# SPI_translators.net
KiCad netlist of a schematic drawn in Altium Designer
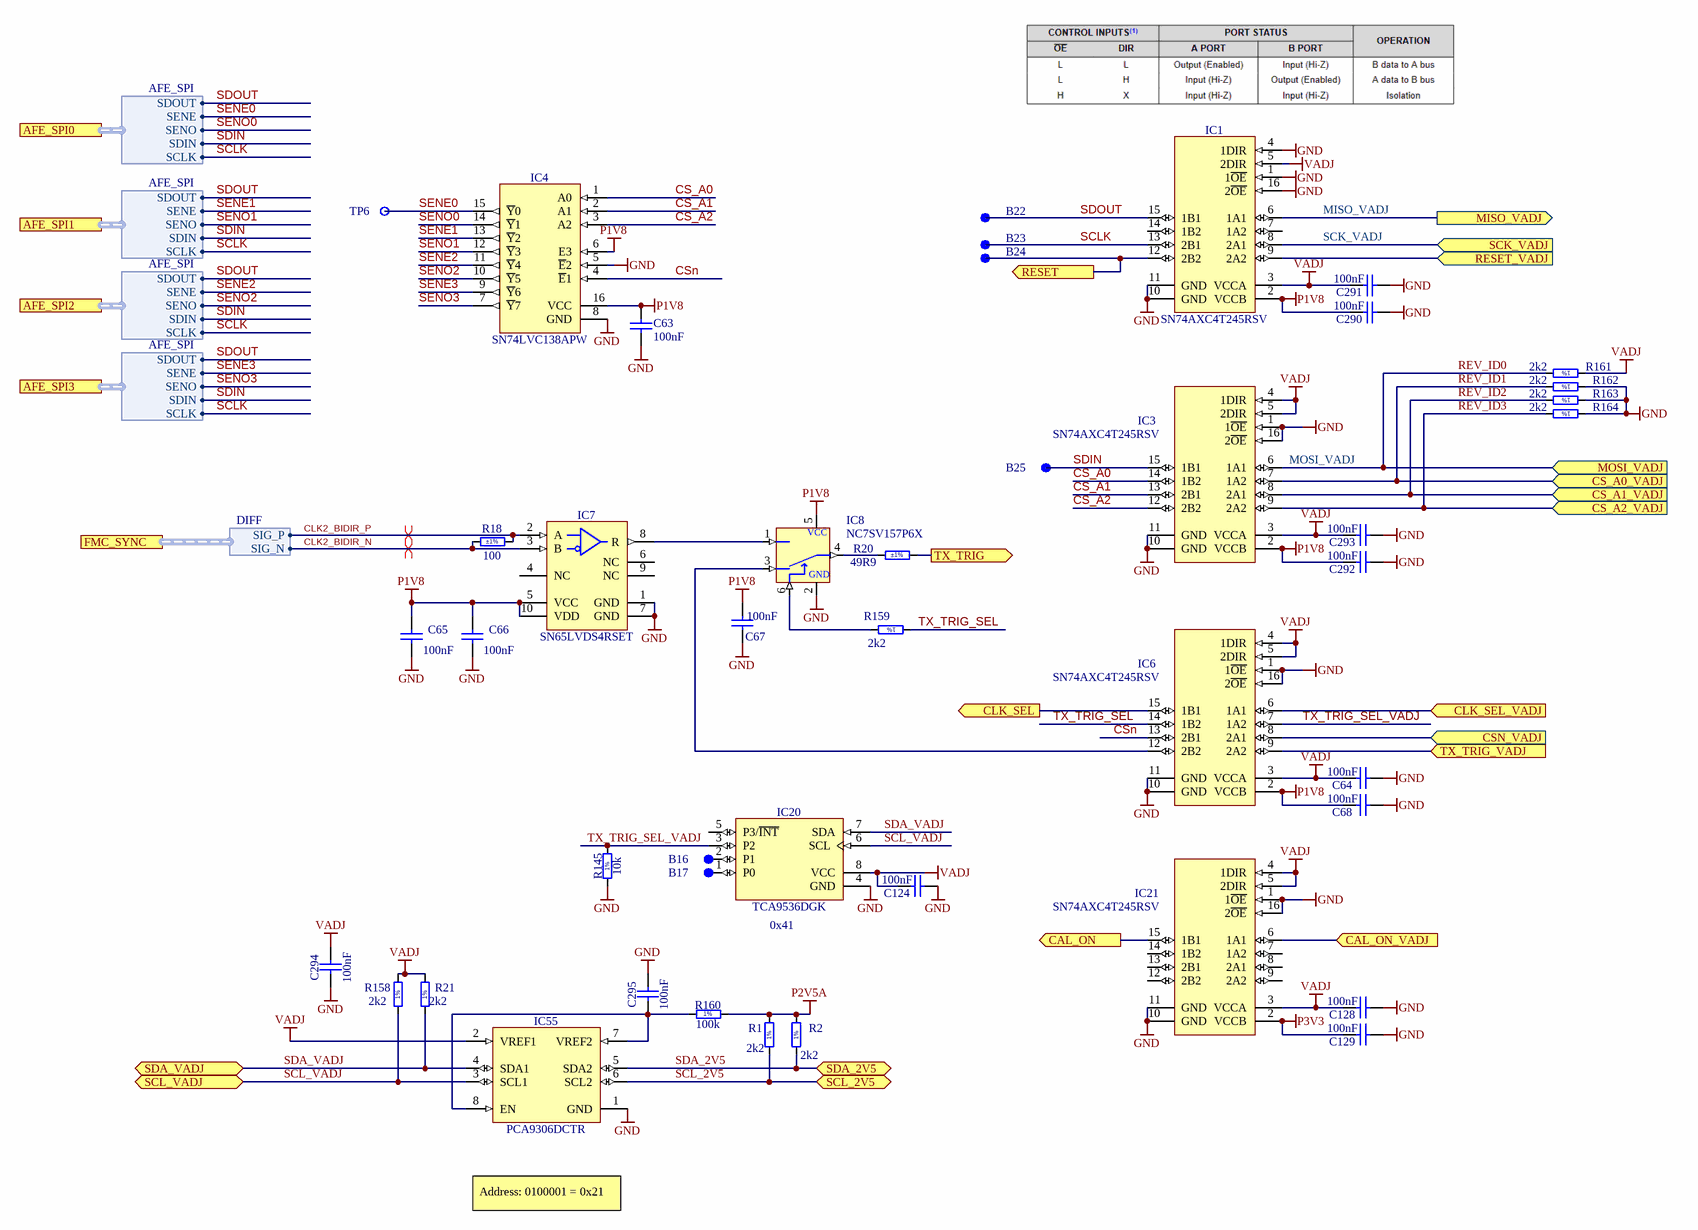
[diagram p0: SPI_translators.SchDoc]

(export (version "E")
  (design (tool "Eeschema 10.0.6"))
  (components
    (comp (ref "B16")
      (value "SMD Pad")
      (footprint "C100")
      (description "Through Hole Pad")
      (fields (field (name "PART NUMBER") "SMD_PAD_D1MM") (field (name "AUTHOR") "CERN DEM JLC"))
      (libsource (lib "Eletro-mechanical") (part "Single SMD Pad (Round)"))
    )
    (comp (ref "B17")
      (value "SMD Pad")
      (footprint "C100")
      (description "Through Hole Pad")
      (fields (field (name "PART NUMBER") "SMD_PAD_D1MM") (field (name "AUTHOR") "CERN DEM JLC"))
      (libsource (lib "Eletro-mechanical") (part "Single SMD Pad (Round)"))
    )
    (comp (ref "B22")
      (value "SMD Pad")
      (footprint "C100")
      (description "Through Hole Pad")
      (fields (field (name "PART NUMBER") "SMD_PAD_D1MM") (field (name "AUTHOR") "CERN DEM JLC"))
      (libsource (lib "Eletro-mechanical") (part "Single SMD Pad (Round)"))
    )
    (comp (ref "B23")
      (value "SMD Pad")
      (footprint "C100")
      (description "Through Hole Pad")
      (fields (field (name "PART NUMBER") "SMD_PAD_D1MM") (field (name "AUTHOR") "CERN DEM JLC"))
      (libsource (lib "Eletro-mechanical") (part "Single SMD Pad (Round)"))
    )
    (comp (ref "B24")
      (value "SMD Pad")
      (footprint "C100")
      (description "Through Hole Pad")
      (fields (field (name "PART NUMBER") "SMD_PAD_D1MM") (field (name "AUTHOR") "CERN DEM JLC"))
      (libsource (lib "Eletro-mechanical") (part "Single SMD Pad (Round)"))
    )
    (comp (ref "B25")
      (value "SMD Pad")
      (footprint "C100")
      (description "Through Hole Pad")
      (fields (field (name "PART NUMBER") "SMD_PAD_D1MM") (field (name "AUTHOR") "CERN DEM JLC"))
      (libsource (lib "Eletro-mechanical") (part "Single SMD Pad (Round)"))
    )
    (comp (ref "C63")
      (value "100nF")
      (footprint "CAPC1005X55N")
      (description "Non-polarised capacitor")
      (fields
        (field (name "PART NUMBER") "CC0402_100NF_16V_10%_X5R")
        (field (name "VOLTAGE") "16V")
        (field (name "AUTHOR") "CERN DEM JLC")
      )
      (libsource (lib "Capacitors") (part "Capacitor - non polarized"))
    )
    (comp (ref "C64")
      (value "100nF")
      (footprint "CAPC0603X33N")
      (description "Non-polarised capacitor")
      (fields
        (field (name "MANUFACTURER PART NUMBER") "CC0201_100NF_6.3V_10%_X5R")
        (field (name "MANUFACTURER") "GENERIC")
        (field (name "AUTHOR") "CERN DEM JLC")
      )
      (libsource (lib "Capacitors") (part "Capacitor - non polarized"))
    )
    (comp (ref "C65")
      (value "100nF")
      (footprint "CAPC0603X33N")
      (description "Non-polarised capacitor")
      (fields
        (field (name "MANUFACTURER PART NUMBER") "CC0201_100NF_6.3V_10%_X5R")
        (field (name "MANUFACTURER") "GENERIC")
        (field (name "AUTHOR") "CERN DEM JLC")
      )
      (libsource (lib "Capacitors") (part "Capacitor - non polarized"))
    )
    (comp (ref "C66")
      (value "100nF")
      (footprint "CAPC0603X33N")
      (description "Non-polarised capacitor")
      (fields
        (field (name "MANUFACTURER PART NUMBER") "CC0201_100NF_6.3V_10%_X5R")
        (field (name "MANUFACTURER") "GENERIC")
        (field (name "AUTHOR") "CERN DEM JLC")
      )
      (libsource (lib "Capacitors") (part "Capacitor - non polarized"))
    )
    (comp (ref "C67")
      (value "100nF")
      (footprint "CAPC0603X33N")
      (description "Non-polarised capacitor")
      (fields
        (field (name "MANUFACTURER PART NUMBER") "CC0201_100NF_6.3V_10%_X5R")
        (field (name "MANUFACTURER") "GENERIC")
        (field (name "AUTHOR") "CERN DEM JLC")
      )
      (libsource (lib "Capacitors") (part "Capacitor - non polarized"))
    )
    (comp (ref "C68")
      (value "100nF")
      (footprint "CAPC0603X33N")
      (description "Non-polarised capacitor")
      (fields
        (field (name "MANUFACTURER PART NUMBER") "CC0201_100NF_6.3V_10%_X5R")
        (field (name "MANUFACTURER") "GENERIC")
        (field (name "AUTHOR") "CERN DEM JLC")
      )
      (libsource (lib "Capacitors") (part "Capacitor - non polarized"))
    )
    (comp (ref "C124")
      (value "100nF")
      (footprint "CAPC0603X33N")
      (description "Non-polarised capacitor")
      (fields
        (field (name "MANUFACTURER PART NUMBER") "CC0201_100NF_6.3V_10%_X5R")
        (field (name "MANUFACTURER") "GENERIC")
        (field (name "AUTHOR") "CERN DEM JLC")
      )
      (libsource (lib "Capacitors") (part "Capacitor - non polarized"))
    )
    (comp (ref "C128")
      (value "100nF")
      (footprint "CAPC0603X33N")
      (description "Non-polarised capacitor")
      (fields
        (field (name "MANUFACTURER PART NUMBER") "CC0201_100NF_6.3V_10%_X5R")
        (field (name "MANUFACTURER") "GENERIC")
        (field (name "AUTHOR") "CERN DEM JLC")
      )
      (libsource (lib "Capacitors") (part "Capacitor - non polarized"))
    )
    (comp (ref "C129")
      (value "100nF")
      (footprint "CAPC0603X33N")
      (description "Non-polarised capacitor")
      (fields
        (field (name "MANUFACTURER PART NUMBER") "CC0201_100NF_6.3V_10%_X5R")
        (field (name "MANUFACTURER") "GENERIC")
        (field (name "AUTHOR") "CERN DEM JLC")
      )
      (libsource (lib "Capacitors") (part "Capacitor - non polarized"))
    )
    (comp (ref "C290")
      (value "100nF")
      (footprint "CAPC0603X33N")
      (description "Non-polarised capacitor")
      (fields
        (field (name "MANUFACTURER PART NUMBER") "CC0201_100NF_6.3V_10%_X5R")
        (field (name "MANUFACTURER") "GENERIC")
        (field (name "AUTHOR") "CERN DEM JLC")
      )
      (libsource (lib "Capacitors") (part "Capacitor - non polarized"))
    )
    (comp (ref "C291")
      (value "100nF")
      (footprint "CAPC0603X33N")
      (description "Non-polarised capacitor")
      (fields
        (field (name "MANUFACTURER PART NUMBER") "CC0201_100NF_6.3V_10%_X5R")
        (field (name "MANUFACTURER") "GENERIC")
        (field (name "AUTHOR") "CERN DEM JLC")
      )
      (libsource (lib "Capacitors") (part "Capacitor - non polarized"))
    )
    (comp (ref "C292")
      (value "100nF")
      (footprint "CAPC0603X33N")
      (description "Non-polarised capacitor")
      (fields
        (field (name "MANUFACTURER PART NUMBER") "CC0201_100NF_6.3V_10%_X5R")
        (field (name "MANUFACTURER") "GENERIC")
        (field (name "AUTHOR") "CERN DEM JLC")
      )
      (libsource (lib "Capacitors") (part "Capacitor - non polarized"))
    )
    (comp (ref "C293")
      (value "100nF")
      (footprint "CAPC0603X33N")
      (description "Non-polarised capacitor")
      (fields
        (field (name "MANUFACTURER PART NUMBER") "CC0201_100NF_6.3V_10%_X5R")
        (field (name "MANUFACTURER") "GENERIC")
        (field (name "AUTHOR") "CERN DEM JLC")
      )
      (libsource (lib "Capacitors") (part "Capacitor - non polarized"))
    )
    (comp (ref "C294")
      (value "100nF")
      (footprint "CAPC0603X33N")
      (description "Non-polarised capacitor")
      (fields
        (field (name "MANUFACTURER PART NUMBER") "CC0201_100NF_6.3V_10%_X5R")
        (field (name "MANUFACTURER") "GENERIC")
        (field (name "AUTHOR") "CERN DEM JLC")
      )
      (libsource (lib "Capacitors") (part "Capacitor - non polarized"))
    )
    (comp (ref "C295")
      (value "100nF")
      (footprint "CAPC0603X33N")
      (description "Non-polarised capacitor")
      (fields
        (field (name "MANUFACTURER PART NUMBER") "CC0201_100NF_6.3V_10%_X5R")
        (field (name "MANUFACTURER") "GENERIC")
        (field (name "AUTHOR") "CERN DEM JLC")
      )
      (libsource (lib "Capacitors") (part "Capacitor - non polarized"))
    )
    (comp (ref "IC1")
      (value "SN74AXC4T245RSV")
      (footprint "QFN40P180X260X55-16N")
      (description "4-Bit Dual-Supply Bus Transceiver with Configurable Voltage Translation and 3-State Output")
      (fields (field (name "MANUFACTURER") "TEXAS INSTRUMENTS") (field (name "AUTHOR") "GK"))
      (libsource (lib "ICS-logic") (part "SN74AXC4T245"))
    )
    (comp (ref "IC3")
      (value "SN74AXC4T245RSV")
      (footprint "QFN40P180X260X55-16N")
      (description "4-Bit Dual-Supply Bus Transceiver with Configurable Voltage Translation and 3-State Output")
      (fields (field (name "MANUFACTURER") "TEXAS INSTRUMENTS") (field (name "AUTHOR") "GK"))
      (libsource (lib "ICS-logic") (part "SN74AXC4T245"))
    )
    (comp (ref "IC4")
      (value "SN74LVC138APW")
      (footprint "SOP65P640X110-16N")
      (description "3-Line to 8-Line Decoder/Demultiplexer")
      (fields (field (name "MANUFACTURER") "Texas Instruments") (field (name "AUTHOR") "GK"))
      (libsource (lib "ICS-logic") (part "SN74LVC138APW"))
    )
    (comp (ref "IC6")
      (value "SN74AXC4T245RSV")
      (footprint "QFN40P180X260X55-16N")
      (description "4-Bit Dual-Supply Bus Transceiver with Configurable Voltage Translation and 3-State Output")
      (fields (field (name "MANUFACTURER") "TEXAS INSTRUMENTS") (field (name "AUTHOR") "GK"))
      (libsource (lib "ICS-logic") (part "SN74AXC4T245"))
    )
    (comp (ref "IC7")
      (value "SN65LVDS4RSET")
      (footprint "TEXAS_RSE (R-PUQFN-N10)")
      (description "1.8V High-Speed Differential Line Receiver")
      (fields (field (name "MANUFACTURER") "TEXAS INSTRUMENTS") (field (name "AUTHOR") "CERN DEM JMW"))
      (libsource (lib "ICs And Semiconductors") (part "SN65LVDS4"))
    )
    (comp (ref "IC8")
      (value "NC7SV157P6X")
      (footprint "SC70-6")
      (description "TinyLogic ULP-A 2-Input Non-Inverting Multiplexer")
      (libsource (lib "ICS-logic") (part "74_NC7SV157P6X"))
    )
    (comp (ref "IC20")
      (value "TCA9536DGK")
      (footprint "SOP65P490X110-8N")
      (description "Remote 4-Bit I2C and SMBus I/O Expander with Configuration Registers")
      (fields (field (name "MANUFACTURER") "TEXAS INSTRUMENTS") (field (name "AUTHOR") "CERN DEM HF"))
      (libsource (lib "ICs And Semiconductors") (part "TCA9536DGK"))
    )
    (comp (ref "IC21")
      (value "SN74AXC4T245RSV")
      (footprint "QFN40P180X260X55-16N")
      (description "4-Bit Dual-Supply Bus Transceiver with Configurable Voltage Translation and 3-State Output")
      (fields (field (name "MANUFACTURER") "TEXAS INSTRUMENTS") (field (name "AUTHOR") "GK"))
      (libsource (lib "ICS-logic") (part "SN74AXC4T245"))
    )
    (comp (ref "IC55")
      (value "PCA9306DCTR")
      (footprint "SOP65P400X130-8N")
      (description "Dual Bidirectional I2C Bus And SMBus Voltage-Level Translator")
      (fields (field (name "MANUFACTURER") "TEXAS INSTRUMENTS") (field (name "AUTHOR") "CERN DEM JLC"))
      (libsource (lib "ICs And Semiconductors") (part "PCA9306DC"))
    )
    (comp (ref "R1")
      (value "2k2")
      (footprint "RESC1005X40N")
      (description "Resistor - 1%")
      (fields
        (field (name "PART NUMBER") "R0402_2K2_1%_0.0625W_100PPM")
        (field (name "POWER") "0.0625W")
        (field (name "AUTHOR") "CERN DEM JLC")
      )
      (libsource (lib "Resistors") (part "Resistor - 1%"))
    )
    (comp (ref "R2")
      (value "2k2")
      (footprint "RESC1005X40N")
      (description "Resistor - 1%")
      (fields
        (field (name "PART NUMBER") "R0402_2K2_1%_0.0625W_100PPM")
        (field (name "POWER") "0.0625W")
        (field (name "AUTHOR") "CERN DEM JLC")
      )
      (libsource (lib "Resistors") (part "Resistor - 1%"))
    )
    (comp (ref "R18")
      (value "100")
      (footprint "RESC1005X40N")
      (description "Resistor - 1%")
      (fields
        (field (name "TOLERANCE") "±1%")
        (field (name "PART NUMBER") "R0402_100R_1%_0.0625W_100PPM")
        (field (name "POWER") "0.0625W")
        (field (name "AUTHOR") "CERN DEM JLC")
      )
      (libsource (lib "Resistors") (part "Resistor - 1%"))
    )
    (comp (ref "R20")
      (value "49R9")
      (footprint "RESC1005X40N")
      (description "Resistor - 1%")
      (fields
        (field (name "TOLERANCE") "±1%")
        (field (name "PART NUMBER") "R0402_49R9_1%_0.0625W_100PPM")
        (field (name "POWER") "0.0625W")
        (field (name "AUTHOR") "CERN DEM JLC")
      )
      (libsource (lib "Resistors") (part "Resistor - 1%"))
    )
    (comp (ref "R21")
      (value "2k2")
      (footprint "RESC1005X40N")
      (description "Resistor - 1%")
      (fields
        (field (name "PART NUMBER") "R0402_2K2_1%_0.0625W_100PPM")
        (field (name "POWER") "0.0625W")
        (field (name "AUTHOR") "CERN DEM JLC")
      )
      (libsource (lib "Resistors") (part "Resistor - 1%"))
    )
    (comp (ref "R145")
      (value "10k")
      (footprint "RESC1005X40N")
      (description "Resistor - 1%")
      (fields
        (field (name "PART NUMBER") "R0402_10K_1%_0.0625W_100PPM")
        (field (name "POWER") "0.0625W")
        (field (name "AUTHOR") "CERN DEM JLC")
      )
      (libsource (lib "Resistors") (part "Resistor - 1%"))
    )
    (comp (ref "R158")
      (value "2k2")
      (footprint "RESC1005X40N")
      (description "Resistor - 1%")
      (fields
        (field (name "PART NUMBER") "R0402_2K2_1%_0.0625W_100PPM")
        (field (name "POWER") "0.0625W")
        (field (name "AUTHOR") "CERN DEM JLC")
      )
      (libsource (lib "Resistors") (part "Resistor - 1%"))
    )
    (comp (ref "R159")
      (value "2k2")
      (footprint "RESC1005X40N")
      (description "Resistor - 1%")
      (fields
        (field (name "PART NUMBER") "R0402_2K2_1%_0.0625W_100PPM")
        (field (name "POWER") "0.0625W")
        (field (name "AUTHOR") "CERN DEM JLC")
      )
      (libsource (lib "Resistors") (part "Resistor - 1%"))
    )
    (comp (ref "R160")
      (value "100k")
      (footprint "RESC1005X40N")
      (description "Resistor - 1%")
      (fields
        (field (name "PART NUMBER") "R0402_100K_1%_0.0625W_100PPM")
        (field (name "POWER") "0.0625W")
        (field (name "AUTHOR") "CERN DEM JLC")
      )
      (libsource (lib "Resistors") (part "Resistor - 1%"))
    )
    (comp (ref "R161")
      (value "2k2")
      (footprint "RESC1005X40N")
      (description "Resistor - 1%")
      (fields
        (field (name "PART NUMBER") "R0402_2K2_1%_0.0625W_100PPM")
        (field (name "POWER") "0.0625W")
        (field (name "AUTHOR") "CERN DEM JLC")
      )
      (libsource (lib "Resistors") (part "Resistor - 1%"))
    )
    (comp (ref "R162")
      (value "2k2")
      (footprint "RESC1005X40N")
      (description "Resistor - 1%")
      (fields
        (field (name "PART NUMBER") "R0402_2K2_1%_0.0625W_100PPM")
        (field (name "POWER") "0.0625W")
        (field (name "AUTHOR") "CERN DEM JLC")
      )
      (libsource (lib "Resistors") (part "Resistor - 1%"))
    )
    (comp (ref "R163")
      (value "2k2")
      (footprint "RESC1005X40N")
      (description "Resistor - 1%")
      (fields
        (field (name "PART NUMBER") "R0402_2K2_1%_0.0625W_100PPM")
        (field (name "POWER") "0.0625W")
        (field (name "AUTHOR") "CERN DEM JLC")
      )
      (libsource (lib "Resistors") (part "Resistor - 1%"))
    )
    (comp (ref "R164")
      (value "2k2")
      (footprint "RESC1005X40N")
      (description "Resistor - 1%")
      (fields
        (field (name "PART NUMBER") "R0402_2K2_1%_0.0625W_100PPM")
        (field (name "POWER") "0.0625W")
        (field (name "AUTHOR") "CERN DEM JLC")
      )
      (libsource (lib "Resistors") (part "Resistor - 1%"))
    )
    (comp (ref "TP6")
      (value "Test Point")
      (footprint "TPS127")
      (fields (field (name "PART NUMBER") "SMD_PAD_1.27X1.27MM") (field (name "AUTHOR") "CERN DEM JLC"))
      (libsource (lib "Eletro-mechanical") (part "Test Point"))
    )
  )
  (nets
    (net (code "3") (name "/CAL_ON") (class "Default")
      (node (ref "IC21") (pin "15") (pinfunction "1B1_15") (pintype "bidirectional"))
    )
    (net (code "4") (name "/CAL_ON_VADJ") (class "Default")
      (node (ref "IC21") (pin "6") (pinfunction "1A1_6") (pintype "bidirectional"))
    )
    (net (code "5") (name "/CLK2_BIDIR_N") (class "Default")
      (node (ref "IC7") (pin "3") (pinfunction "B_3") (pintype "input"))
      (node (ref "R18") (pin "1") (pinfunction "1_1") (pintype "passive"))
    )
    (net (code "6") (name "/CLK2_BIDIR_P") (class "Default")
      (node (ref "IC7") (pin "2") (pinfunction "A_2") (pintype "input"))
      (node (ref "R18") (pin "2") (pinfunction "2_2") (pintype "passive"))
    )
    (net (code "7") (name "/CLK_SEL") (class "Default")
      (node (ref "IC6") (pin "15") (pinfunction "1B1_15") (pintype "bidirectional"))
    )
    (net (code "8") (name "/CLK_SEL_VADJ") (class "Default")
      (node (ref "IC6") (pin "6") (pinfunction "1A1_6") (pintype "bidirectional"))
    )
    (net (code "9") (name "/CSN_VADJ") (class "Default")
      (node (ref "IC6") (pin "8") (pinfunction "2A1_8") (pintype "bidirectional"))
    )
    (net (code "10") (name "/CS_A0") (class "Default")
      (node (ref "IC3") (pin "14") (pinfunction "1B2_14") (pintype "bidirectional"))
      (node (ref "IC4") (pin "1") (pinfunction "A0_1") (pintype "input"))
    )
    (net (code "11") (name "/CS_A1") (class "Default")
      (node (ref "IC3") (pin "13") (pinfunction "2B1_13") (pintype "bidirectional"))
      (node (ref "IC4") (pin "2") (pinfunction "A1_2") (pintype "input"))
    )
    (net (code "12") (name "/CS_A2") (class "Default")
      (node (ref "IC3") (pin "12") (pinfunction "2B2_12") (pintype "bidirectional"))
      (node (ref "IC4") (pin "3") (pinfunction "A2_3") (pintype "input"))
    )
    (net (code "13") (name "/CSn") (class "Default")
      (node (ref "IC4") (pin "4") (pinfunction "~{E}1_4") (pintype "input"))
      (node (ref "IC6") (pin "13") (pinfunction "2B1_13") (pintype "bidirectional"))
    )
    (net (code "14") (name "/MISO_VADJ") (class "Default")
      (node (ref "IC1") (pin "6") (pinfunction "1A1_6") (pintype "bidirectional"))
    )
    (net (code "15") (name "/MOSI_VADJ") (class "Default")
      (node (ref "IC3") (pin "6") (pinfunction "1A1_6") (pintype "bidirectional"))
      (node (ref "R161") (pin "2") (pinfunction "2_2") (pintype "passive"))
    )
    (net (code "16") (name "/RESET") (class "Default")
      (node (ref "B24") (pin "1") (pinfunction "1_1") (pintype "bidirectional"))
      (node (ref "IC1") (pin "12") (pinfunction "2B2_12") (pintype "bidirectional"))
    )
    (net (code "17") (name "/RESET_VADJ") (class "Default")
      (node (ref "IC1") (pin "9") (pinfunction "2A2_9") (pintype "bidirectional"))
    )
    (net (code "18") (name "/REV_ID1") (class "Default")
      (node (ref "IC3") (pin "7") (pinfunction "1A2_7") (pintype "bidirectional"))
      (node (ref "R162") (pin "2") (pinfunction "2_2") (pintype "passive"))
    )
    (net (code "19") (name "/REV_ID2") (class "Default")
      (node (ref "IC3") (pin "8") (pinfunction "2A1_8") (pintype "bidirectional"))
      (node (ref "R163") (pin "2") (pinfunction "2_2") (pintype "passive"))
    )
    (net (code "20") (name "/REV_ID3") (class "Default")
      (node (ref "IC3") (pin "9") (pinfunction "2A2_9") (pintype "bidirectional"))
      (node (ref "R164") (pin "2") (pinfunction "2_2") (pintype "passive"))
    )
    (net (code "21") (name "/SCK_VADJ") (class "Default")
      (node (ref "IC1") (pin "8") (pinfunction "2A1_8") (pintype "bidirectional"))
    )
    (net (code "22") (name "/SCLK") (class "Default")
      (node (ref "B23") (pin "1") (pinfunction "1_1") (pintype "bidirectional"))
      (node (ref "IC1") (pin "13") (pinfunction "2B1_13") (pintype "bidirectional"))
    )
    (net (code "23") (name "/SCL_2V5") (class "Default")
      (node (ref "IC55") (pin "6") (pinfunction "SCL2_6") (pintype "bidirectional"))
      (node (ref "R1") (pin "1") (pinfunction "1_1") (pintype "passive"))
    )
    (net (code "24") (name "/SCL_VADJ") (class "Default")
      (node (ref "IC20") (pin "6") (pinfunction "SCL_6") (pintype "input"))
      (node (ref "IC55") (pin "3") (pinfunction "SCL1_3") (pintype "bidirectional"))
      (node (ref "R158") (pin "1") (pinfunction "1_1") (pintype "passive"))
    )
    (net (code "25") (name "/SDA_2V5") (class "Default")
      (node (ref "IC55") (pin "5") (pinfunction "SDA2_5") (pintype "bidirectional"))
      (node (ref "R2") (pin "1") (pinfunction "1_1") (pintype "passive"))
    )
    (net (code "26") (name "/SDA_VADJ") (class "Default")
      (node (ref "IC20") (pin "7") (pinfunction "SDA_7") (pintype "input"))
      (node (ref "IC55") (pin "4") (pinfunction "SDA1_4") (pintype "bidirectional"))
      (node (ref "R21") (pin "1") (pinfunction "1_1") (pintype "passive"))
    )
    (net (code "27") (name "/SDIN") (class "Default")
      (node (ref "B25") (pin "1") (pinfunction "1_1") (pintype "bidirectional"))
      (node (ref "IC3") (pin "15") (pinfunction "1B1_15") (pintype "bidirectional"))
    )
    (net (code "28") (name "/SDOUT") (class "Default")
      (node (ref "B22") (pin "1") (pinfunction "1_1") (pintype "bidirectional"))
      (node (ref "IC1") (pin "15") (pinfunction "1B1_15") (pintype "bidirectional"))
    )
    (net (code "29") (name "/SENE0") (class "Default")
      (node (ref "IC4") (pin "15") (pinfunction "~{Y}0_15") (pintype "output"))
      (node (ref "TP6") (pin "1") (pinfunction "1_1") (pintype "bidirectional"))
    )
    (net (code "30") (name "/SENE1") (class "Default")
      (node (ref "IC4") (pin "13") (pinfunction "~{Y}2_13") (pintype "output"))
    )
    (net (code "31") (name "/SENE2") (class "Default")
      (node (ref "IC4") (pin "11") (pinfunction "~{Y}4_11") (pintype "output"))
    )
    (net (code "32") (name "/SENE3") (class "Default")
      (node (ref "IC4") (pin "9") (pinfunction "~{Y}6_9") (pintype "output"))
    )
    (net (code "33") (name "/SENO0") (class "Default")
      (node (ref "IC4") (pin "14") (pinfunction "~{Y}1_14") (pintype "output"))
    )
    (net (code "34") (name "/SENO1") (class "Default")
      (node (ref "IC4") (pin "12") (pinfunction "~{Y}3_12") (pintype "output"))
    )
    (net (code "35") (name "/SENO2") (class "Default")
      (node (ref "IC4") (pin "10") (pinfunction "~{Y}5_10") (pintype "output"))
    )
    (net (code "36") (name "/SENO3") (class "Default")
      (node (ref "IC4") (pin "7") (pinfunction "~{Y}7_7") (pintype "output"))
    )
    (net (code "37") (name "/TX_TRIG") (class "Default")
      (node (ref "R20") (pin "2") (pinfunction "2_2") (pintype "passive"))
    )
    (net (code "38") (name "/TX_TRIG_SEL") (class "Default")
      (node (ref "IC6") (pin "14") (pinfunction "1B2_14") (pintype "bidirectional"))
      (node (ref "R159") (pin "1") (pinfunction "1_1") (pintype "passive"))
    )
    (net (code "39") (name "/TX_TRIG_SEL_VADJ") (class "Default")
      (node (ref "IC20") (pin "3") (pinfunction "P2_3") (pintype "bidirectional"))
      (node (ref "IC6") (pin "7") (pinfunction "1A2_7") (pintype "bidirectional"))
      (node (ref "R145") (pin "2") (pinfunction "2_2") (pintype "passive"))
    )
    (net (code "40") (name "/TX_TRIG_VADJ") (class "Default")
      (node (ref "IC6") (pin "9") (pinfunction "2A2_9") (pintype "bidirectional"))
    )
    (net (code "43") (name "GND") (class "Default")
      (node (ref "C124") (pin "2") (pinfunction "2_2") (pintype "passive"))
      (node (ref "C128") (pin "2") (pinfunction "2_2") (pintype "passive"))
      (node (ref "C129") (pin "2") (pinfunction "2_2") (pintype "passive"))
      (node (ref "C290") (pin "2") (pinfunction "2_2") (pintype "passive"))
      (node (ref "C291") (pin "2") (pinfunction "2_2") (pintype "passive"))
      (node (ref "C292") (pin "2") (pinfunction "2_2") (pintype "passive"))
      (node (ref "C293") (pin "2") (pinfunction "2_2") (pintype "passive"))
      (node (ref "C294") (pin "1") (pinfunction "1_1") (pintype "passive"))
      (node (ref "C295") (pin "2") (pinfunction "2_2") (pintype "passive"))
      (node (ref "C63") (pin "1") (pinfunction "1_1") (pintype "passive"))
      (node (ref "C64") (pin "2") (pinfunction "2_2") (pintype "passive"))
      (node (ref "C65") (pin "2") (pinfunction "2_2") (pintype "passive"))
      (node (ref "C66") (pin "2") (pinfunction "2_2") (pintype "passive"))
      (node (ref "C67") (pin "1") (pinfunction "1_1") (pintype "passive"))
      (node (ref "C68") (pin "2") (pinfunction "2_2") (pintype "passive"))
      (node (ref "IC1") (pin "1") (pinfunction "1~{OE}_1") (pintype "input"))
      (node (ref "IC1") (pin "10") (pinfunction "GND_10") (pintype "power_in"))
      (node (ref "IC1") (pin "11") (pinfunction "GND_11") (pintype "power_in"))
      (node (ref "IC1") (pin "16") (pinfunction "2~{OE}_16") (pintype "input"))
      (node (ref "IC1") (pin "4") (pinfunction "1DIR_4") (pintype "input"))
      (node (ref "IC20") (pin "4") (pinfunction "GND_4") (pintype "power_in"))
      (node (ref "IC21") (pin "1") (pinfunction "1~{OE}_1") (pintype "input"))
      (node (ref "IC21") (pin "10") (pinfunction "GND_10") (pintype "power_in"))
      (node (ref "IC21") (pin "11") (pinfunction "GND_11") (pintype "power_in"))
      (node (ref "IC21") (pin "16") (pinfunction "2~{OE}_16") (pintype "input"))
      (node (ref "IC3") (pin "1") (pinfunction "1~{OE}_1") (pintype "input"))
      (node (ref "IC3") (pin "10") (pinfunction "GND_10") (pintype "power_in"))
      (node (ref "IC3") (pin "11") (pinfunction "GND_11") (pintype "power_in"))
      (node (ref "IC3") (pin "16") (pinfunction "2~{OE}_16") (pintype "input"))
      (node (ref "IC4") (pin "5") (pinfunction "~{E}2_5") (pintype "input"))
      (node (ref "IC4") (pin "8") (pinfunction "GND_8") (pintype "power_in"))
      (node (ref "IC55") (pin "1") (pinfunction "GND_1") (pintype "power_in"))
      (node (ref "IC6") (pin "1") (pinfunction "1~{OE}_1") (pintype "input"))
      (node (ref "IC6") (pin "10") (pinfunction "GND_10") (pintype "power_in"))
      (node (ref "IC6") (pin "11") (pinfunction "GND_11") (pintype "power_in"))
      (node (ref "IC6") (pin "16") (pinfunction "2~{OE}_16") (pintype "input"))
      (node (ref "IC7") (pin "1") (pinfunction "GND_1") (pintype "power_in"))
      (node (ref "IC7") (pin "7") (pinfunction "GND_7") (pintype "power_in"))
      (node (ref "IC8") (pin "2") (pinfunction "GND_2") (pintype "power_in"))
      (node (ref "R145") (pin "1") (pinfunction "1_1") (pintype "passive"))
      (node (ref "R162") (pin "1") (pinfunction "1_1") (pintype "passive"))
      (node (ref "R163") (pin "1") (pinfunction "1_1") (pintype "passive"))
      (node (ref "R164") (pin "1") (pinfunction "1_1") (pintype "passive"))
    )
    (net (code "44") (name "Net-(IC6-2B2)") (class "Default")
      (node (ref "IC6") (pin "12") (pinfunction "2B2_12") (pintype "bidirectional"))
      (node (ref "IC8") (pin "3") (pinfunction "I0_3") (pintype "input"))
    )
    (net (code "45") (name "Net-(IC7-R)") (class "Default")
      (node (ref "IC7") (pin "8") (pinfunction "R_8") (pintype "output"))
      (node (ref "IC8") (pin "1") (pinfunction "I1_1") (pintype "input"))
    )
    (net (code "46") (name "Net-(IC8-S)") (class "Default")
      (node (ref "IC8") (pin "6") (pinfunction "S_6") (pintype "input"))
      (node (ref "R159") (pin "2") (pinfunction "2_2") (pintype "passive"))
    )
    (net (code "47") (name "Net-(IC8-Z)") (class "Default")
      (node (ref "IC8") (pin "4") (pinfunction "Z_4") (pintype "output"))
      (node (ref "R20") (pin "1") (pinfunction "1_1") (pintype "passive"))
    )
    (net (code "48") (name "Net-(IC20-P0)") (class "Default")
      (node (ref "B17") (pin "1") (pinfunction "1_1") (pintype "bidirectional"))
      (node (ref "IC20") (pin "1") (pinfunction "P0_1") (pintype "bidirectional"))
    )
    (net (code "49") (name "Net-(IC20-P1)") (class "Default")
      (node (ref "B16") (pin "1") (pinfunction "1_1") (pintype "bidirectional"))
      (node (ref "IC20") (pin "2") (pinfunction "P1_2") (pintype "bidirectional"))
    )
    (net (code "50") (name "Net-(IC55-EN)") (class "Default")
      (node (ref "C295") (pin "1") (pinfunction "1_1") (pintype "passive"))
      (node (ref "IC55") (pin "7") (pinfunction "VREF2_7") (pintype "input"))
      (node (ref "IC55") (pin "8") (pinfunction "EN_8") (pintype "input"))
      (node (ref "R160") (pin "1") (pinfunction "1_1") (pintype "passive"))
    )
    (net (code "51") (name "P1V8") (class "Default")
      (node (ref "C290") (pin "1") (pinfunction "1_1") (pintype "passive"))
      (node (ref "C292") (pin "1") (pinfunction "1_1") (pintype "passive"))
      (node (ref "C63") (pin "2") (pinfunction "2_2") (pintype "passive"))
      (node (ref "C65") (pin "1") (pinfunction "1_1") (pintype "passive"))
      (node (ref "C66") (pin "1") (pinfunction "1_1") (pintype "passive"))
      (node (ref "C67") (pin "2") (pinfunction "2_2") (pintype "passive"))
      (node (ref "C68") (pin "1") (pinfunction "1_1") (pintype "passive"))
      (node (ref "IC1") (pin "2") (pinfunction "VCCB_2") (pintype "power_in"))
      (node (ref "IC3") (pin "2") (pinfunction "VCCB_2") (pintype "power_in"))
      (node (ref "IC4") (pin "16") (pinfunction "VCC_16") (pintype "power_in"))
      (node (ref "IC4") (pin "6") (pinfunction "E3_6") (pintype "input"))
      (node (ref "IC6") (pin "2") (pinfunction "VCCB_2") (pintype "power_in"))
      (node (ref "IC7") (pin "10") (pinfunction "VDD_10") (pintype "power_in"))
      (node (ref "IC7") (pin "5") (pinfunction "VCC_5") (pintype "power_in"))
      (node (ref "IC8") (pin "5") (pinfunction "Vcc_5") (pintype "power_in"))
    )
    (net (code "52") (name "P2V5A") (class "Default")
      (node (ref "R1") (pin "2") (pinfunction "2_2") (pintype "passive"))
      (node (ref "R160") (pin "2") (pinfunction "2_2") (pintype "passive"))
      (node (ref "R2") (pin "2") (pinfunction "2_2") (pintype "passive"))
    )
    (net (code "53") (name "P3V3") (class "Default")
      (node (ref "C129") (pin "1") (pinfunction "1_1") (pintype "passive"))
      (node (ref "IC21") (pin "2") (pinfunction "VCCB_2") (pintype "power_in"))
    )
    (net (code "54") (name "VADJ") (class "Default")
      (node (ref "C124") (pin "1") (pinfunction "1_1") (pintype "passive"))
      (node (ref "C128") (pin "1") (pinfunction "1_1") (pintype "passive"))
      (node (ref "C291") (pin "1") (pinfunction "1_1") (pintype "passive"))
      (node (ref "C293") (pin "1") (pinfunction "1_1") (pintype "passive"))
      (node (ref "C294") (pin "2") (pinfunction "2_2") (pintype "passive"))
      (node (ref "C64") (pin "1") (pinfunction "1_1") (pintype "passive"))
      (node (ref "IC1") (pin "3") (pinfunction "VCCA_3") (pintype "power_in"))
      (node (ref "IC1") (pin "5") (pinfunction "2DIR_5") (pintype "input"))
      (node (ref "IC20") (pin "8") (pinfunction "VCC_8") (pintype "power_in"))
      (node (ref "IC21") (pin "3") (pinfunction "VCCA_3") (pintype "power_in"))
      (node (ref "IC21") (pin "4") (pinfunction "1DIR_4") (pintype "input"))
      (node (ref "IC21") (pin "5") (pinfunction "2DIR_5") (pintype "input"))
      (node (ref "IC3") (pin "3") (pinfunction "VCCA_3") (pintype "power_in"))
      (node (ref "IC3") (pin "4") (pinfunction "1DIR_4") (pintype "input"))
      (node (ref "IC3") (pin "5") (pinfunction "2DIR_5") (pintype "input"))
      (node (ref "IC55") (pin "2") (pinfunction "VREF1_2") (pintype "input"))
      (node (ref "IC6") (pin "3") (pinfunction "VCCA_3") (pintype "power_in"))
      (node (ref "IC6") (pin "4") (pinfunction "1DIR_4") (pintype "input"))
      (node (ref "IC6") (pin "5") (pinfunction "2DIR_5") (pintype "input"))
      (node (ref "R158") (pin "2") (pinfunction "2_2") (pintype "passive"))
      (node (ref "R161") (pin "1") (pinfunction "1_1") (pintype "passive"))
      (node (ref "R21") (pin "2") (pinfunction "2_2") (pintype "passive"))
    )
    (net (code "55") (name "unconnected-(IC1-1A2-Pad7)") (class "Default")
      (node (ref "IC1") (pin "7") (pinfunction "1A2_7") (pintype "bidirectional"))
    )
    (net (code "56") (name "unconnected-(IC1-1B2-Pad14)") (class "Default")
      (node (ref "IC1") (pin "14") (pinfunction "1B2_14") (pintype "bidirectional"))
    )
    (net (code "57") (name "unconnected-(IC7-NC-Pad4)") (class "Default")
      (node (ref "IC7") (pin "4") (pinfunction "NC_4") (pintype "passive"))
    )
    (net (code "58") (name "unconnected-(IC7-NC-Pad6)") (class "Default")
      (node (ref "IC7") (pin "6") (pinfunction "NC_6") (pintype "passive"))
    )
    (net (code "59") (name "unconnected-(IC7-NC-Pad9)") (class "Default")
      (node (ref "IC7") (pin "9") (pinfunction "NC_9") (pintype "passive"))
    )
    (net (code "60") (name "unconnected-(IC20-P3{slash}~{INT}-Pad5)") (class "Default")
      (node (ref "IC20") (pin "5") (pinfunction "P3/~{INT}_5") (pintype "bidirectional"))
    )
    (net (code "61") (name "unconnected-(IC21-1A2-Pad7)") (class "Default")
      (node (ref "IC21") (pin "7") (pinfunction "1A2_7") (pintype "bidirectional"))
    )
    (net (code "62") (name "unconnected-(IC21-1B2-Pad14)") (class "Default")
      (node (ref "IC21") (pin "14") (pinfunction "1B2_14") (pintype "bidirectional"))
    )
    (net (code "63") (name "unconnected-(IC21-2A1-Pad8)") (class "Default")
      (node (ref "IC21") (pin "8") (pinfunction "2A1_8") (pintype "bidirectional"))
    )
    (net (code "64") (name "unconnected-(IC21-2A2-Pad9)") (class "Default")
      (node (ref "IC21") (pin "9") (pinfunction "2A2_9") (pintype "bidirectional"))
    )
    (net (code "65") (name "unconnected-(IC21-2B1-Pad13)") (class "Default")
      (node (ref "IC21") (pin "13") (pinfunction "2B1_13") (pintype "bidirectional"))
    )
    (net (code "66") (name "unconnected-(IC21-2B2-Pad12)") (class "Default")
      (node (ref "IC21") (pin "12") (pinfunction "2B2_12") (pintype "bidirectional"))
    )
  )
)
